# Raspberry_DC-HD_v1.net
KiCad netlist of a schematic drawn in Altium Designer
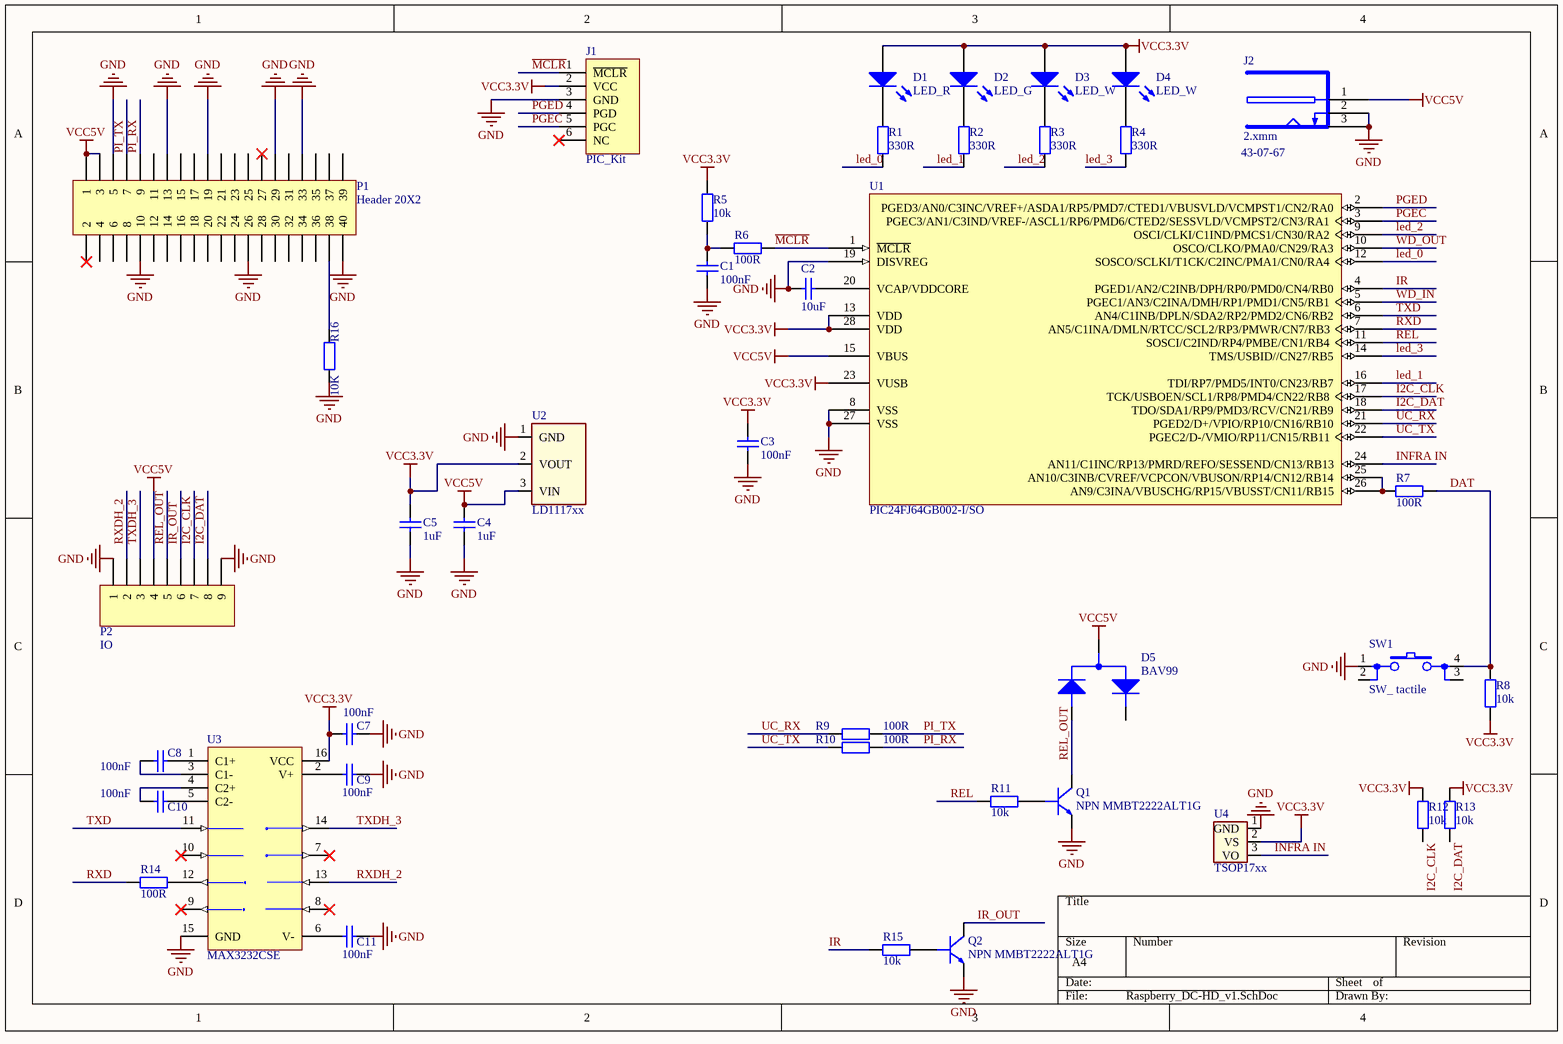
[diagram p0: Raspberry_DC-HD_v1.SchDoc]

(export (version "E")
  (design (tool "Eeschema 10.0.6"))
  (components
    (comp (ref "C1")
      (value "100nF")
      (footprint "FP_0603_CAP_080")
      (description "Capacitor")
      (libsource (lib "Capacitor") (part "CAP"))
    )
    (comp (ref "C2")
      (value "10uF")
      (footprint "FP_0603_CAP_080")
      (description "Capacitor")
      (libsource (lib "Capacitor") (part "CAP"))
    )
    (comp (ref "C3")
      (value "100nF")
      (footprint "FP_0603_CAP_080")
      (description "Capacitor")
      (libsource (lib "Capacitor") (part "CAP"))
    )
    (comp (ref "C4")
      (value "1uF")
      (footprint "FP_0603_CAP_080")
      (description "Capacitor")
      (libsource (lib "Capacitor") (part "CAP"))
    )
    (comp (ref "C5")
      (value "1uF")
      (footprint "FP_0603_CAP_080")
      (description "Capacitor")
      (libsource (lib "Capacitor") (part "CAP"))
    )
    (comp (ref "C7")
      (value "100nF")
      (footprint "FP_0603_CAP_080")
      (description "Capacitor")
      (libsource (lib "Capacitor") (part "CAP"))
    )
    (comp (ref "C8")
      (value "100nF")
      (footprint "FP_0603_CAP_080")
      (description "Capacitor")
      (libsource (lib "Capacitor") (part "CAP"))
    )
    (comp (ref "C9")
      (value "100nF")
      (footprint "FP_0603_CAP_080")
      (description "Capacitor")
      (libsource (lib "Capacitor") (part "CAP"))
    )
    (comp (ref "C10")
      (value "100nF")
      (footprint "FP_0603_CAP_080")
      (description "Capacitor")
      (libsource (lib "Capacitor") (part "CAP"))
    )
    (comp (ref "C11")
      (value "100nF")
      (footprint "FP_0603_CAP_080")
      (description "Capacitor")
      (libsource (lib "Capacitor") (part "CAP"))
    )
    (comp (ref "D1")
      (value "LED_R")
      (footprint "1206 LED Reversed")
      (description "Typical LED")
      (libsource (lib "Led_optical") (part "LED"))
    )
    (comp (ref "D2")
      (value "LED_G")
      (footprint "1206 LED Reversed")
      (description "Typical LED")
      (libsource (lib "Led_optical") (part "LED"))
    )
    (comp (ref "D3")
      (value "LED_W")
      (footprint "1206 LED Reversed")
      (description "Typical LED")
      (libsource (lib "Led_optical") (part "LED"))
    )
    (comp (ref "D4")
      (value "LED_W")
      (footprint "1206 LED Reversed")
      (description "Typical LED")
      (libsource (lib "Led_optical") (part "LED"))
    )
    (comp (ref "D5")
      (value "BAV99")
      (footprint "DIODE_SOT23_serial")
      (libsource (lib "Diode") (part "BAV99"))
    )
    (comp (ref "J1")
      (value "PIC_Kit")
      (footprint "HDR1X6")
      (description "PIC Kit connector")
      (libsource (lib "EtherIOv2") (part "PIC_Kit"))
    )
    (comp (ref "J2")
      (value "2.xmm")
      (footprint "FP_DC_TAP_ANYA")
      (description "2.xmm DC HEBA25 TÁPFESZÜLTSÉG ALJZAT ZÁRT, NYÁKBA 90°")
      (fields (field (name "ORDER INFO") "43-07-67"))
      (libsource (lib "Connector") (part "DC_TAP_ANYA"))
    )
    (comp (ref "P1")
      (value "Header 20X2")
      (footprint "Header_2X20_pin_2.54")
      (description "Header, 20-Pin, Dual row")
      (fields (field (name "PUBLISHER") "Altium Limited"))
      (libsource (lib "Miscellaneous Connectors") (part "Header 20X2"))
    )
    (comp (ref "P2")
      (value "IO")
      (footprint "Euroblock 3.5pitch 9P")
      (description "Header, 9-Pin")
      (fields (field (name "PUBLISHER") "Altium Limited"))
      (libsource (lib "Miscellaneous Connectors") (part "Header 9"))
    )
    (comp (ref "Q1")
      (value "NPN MMBT2222ALT1G")
      (footprint "TR_SOT23")
      (libsource (lib "Transistor") (part "NPN"))
    )
    (comp (ref "Q2")
      (value "NPN MMBT2222ALT1G")
      (footprint "TR_SOT23")
      (libsource (lib "Transistor") (part "NPN"))
    )
    (comp (ref "R1")
      (value "330R")
      (footprint "FP_0603_RES")
      (description "Resistor")
      (libsource (lib "Resistor") (part "RES"))
    )
    (comp (ref "R2")
      (value "330R")
      (footprint "FP_0603_RES")
      (description "Resistor")
      (libsource (lib "Resistor") (part "RES"))
    )
    (comp (ref "R3")
      (value "330R")
      (footprint "FP_0603_RES")
      (description "Resistor")
      (libsource (lib "Resistor") (part "RES"))
    )
    (comp (ref "R4")
      (value "330R")
      (footprint "FP_0603_RES")
      (description "Resistor")
      (libsource (lib "Resistor") (part "RES"))
    )
    (comp (ref "R5")
      (value "10k")
      (footprint "FP_0603_RES")
      (description "Resistor")
      (libsource (lib "") (part "Res3_1"))
    )
    (comp (ref "R6")
      (value "100R")
      (footprint "FP_0603_RES")
      (description "Resistor")
      (libsource (lib "") (part "RES_1"))
    )
    (comp (ref "R7")
      (value "100R")
      (footprint "FP_0603_RES")
      (description "Resistor")
      (libsource (lib "") (part "RES_1"))
    )
    (comp (ref "R8")
      (value "10k")
      (footprint "FP_0603_RES")
      (description "Resistor")
      (libsource (lib "") (part "Res3_1"))
    )
    (comp (ref "R9")
      (value "100R")
      (footprint "FP_0603_RES")
      (description "Resistor")
      (libsource (lib "") (part "RES_1"))
    )
    (comp (ref "R10")
      (value "100R")
      (footprint "FP_0603_RES")
      (description "Resistor")
      (libsource (lib "") (part "RES_1"))
    )
    (comp (ref "R11")
      (value "10k")
      (footprint "FP_0603_RES")
      (description "Resistor")
      (libsource (lib "Miscellaneous Devices") (part "Res3"))
    )
    (comp (ref "R12")
      (value "10k")
      (footprint "FP_0603_RES")
      (description "Resistor")
      (libsource (lib "") (part "Res3_1"))
    )
    (comp (ref "R13")
      (value "10k")
      (footprint "FP_0603_RES")
      (description "Resistor")
      (libsource (lib "") (part "Res3_1"))
    )
    (comp (ref "R14")
      (value "100R")
      (footprint "FP_0603_RES")
      (description "Resistor")
      (libsource (lib "") (part "RES_1"))
    )
    (comp (ref "R15")
      (value "10k")
      (footprint "FP_0603_RES")
      (description "Resistor")
      (libsource (lib "Miscellaneous Devices") (part "Res3"))
    )
    (comp (ref "R16")
      (value "10K")
      (footprint "FP_0603_RES")
      (description "Resistor")
      (libsource (lib "") (part "RES_2"))
    )
    (comp (ref "SW1")
      (value "SW_ tactile")
      (footprint "flat_smd_button")
      (libsource (lib "Switch") (part "SW_ tactile"))
    )
    (comp (ref "U1")
      (value "PIC24FJ64GB002-I/SO")
      (footprint "SSOP-28")
      (fields (field (name "PUBLISHER") "Altium Limited"))
      (libsource (lib "Waterstars") (part "PIC24FJ64GB002-I/SO"))
    )
    (comp (ref "U2")
      (value "LD1117xx")
      (footprint "SUPPLY_SOT223")
      (description "LD1117xx 3,3V lin reg")
      (libsource (lib "Supply") (part "LD1117xx"))
    )
    (comp (ref "U3")
      (value "MAX3232CSE")
      (footprint "DIGITAL_SOIC16")
      (description "3.0V TO 5.5V, Low-Power, up to 1Mbps, True RS-232 Transceiver Using Four 0.1µF External Capacitor")
      (fields (field (name "PUBLISHER") "Altium Limited"))
      (libsource (lib "Maxim Communication Transceiver") (part "MAX3232CSE"))
    )
    (comp (ref "U4")
      (value "TSOP17xx")
      (footprint "TSOP17xx")
      (description "TSOP17xx IR receiver")
      (libsource (lib "Sensor") (part "TSOP17xx"))
    )
  )
  (nets
    (net (code "1") (name "/DAT") (class "Default")
      (node (ref "R7") (pin "1") (pinfunction "1_1") (pintype "passive"))
      (node (ref "R8") (pin "1") (pinfunction "1_1") (pintype "passive"))
      (node (ref "SW1") (pin "4") (pinfunction "4_4") (pintype "passive"))
    )
    (net (code "2") (name "/I2C_CLK") (class "Default")
      (node (ref "P2") (pin "7") (pinfunction "7_7") (pintype "passive"))
      (node (ref "R12") (pin "2") (pinfunction "2_2") (pintype "passive"))
      (node (ref "U1") (pin "17") (pinfunction "TCK/USBOEN/SCL1/RP8/PMD4/CN22/RB8_17") (pintype "bidirectional"))
    )
    (net (code "3") (name "/I2C_DAT") (class "Default")
      (node (ref "P2") (pin "8") (pinfunction "8_8") (pintype "passive"))
      (node (ref "R13") (pin "2") (pinfunction "2_2") (pintype "passive"))
      (node (ref "U1") (pin "18") (pinfunction "TDO/SDA1/RP9/PMD3/RCV/CN21/RB9_18") (pintype "bidirectional"))
    )
    (net (code "4") (name "/INFRA IN") (class "Default")
      (node (ref "U1") (pin "24") (pinfunction "AN11/C1INC/RP13/PMRD/REFO/SESSEND/CN13/RB13_24") (pintype "bidirectional"))
      (node (ref "U4") (pin "3") (pinfunction "VO_3") (pintype "passive"))
    )
    (net (code "5") (name "/IR") (class "Default")
      (node (ref "R15") (pin "1") (pinfunction "1_1") (pintype "passive"))
      (node (ref "U1") (pin "4") (pinfunction "PGED1/AN2/C2INB/DPH/RP0/PMD0/CN4/RB0_4") (pintype "bidirectional"))
    )
    (net (code "6") (name "/IR_OUT") (class "Default")
      (node (ref "P2") (pin "6") (pinfunction "6_6") (pintype "passive"))
      (node (ref "Q2") (pin "C") (pinfunction "C_C") (pintype "passive"))
    )
    (net (code "7") (name "/PGEC") (class "Default")
      (node (ref "J1") (pin "5") (pinfunction "PGC_5") (pintype "passive"))
      (node (ref "U1") (pin "3") (pinfunction "PGEC3/AN1/C3IND/VREF-/ASCL1/RP6/PMD6/CTED2/SESSVLD/VCMPST2/CN3/RA1_3") (pintype "bidirectional"))
    )
    (net (code "8") (name "/PGED") (class "Default")
      (node (ref "J1") (pin "4") (pinfunction "PGD_4") (pintype "passive"))
      (node (ref "U1") (pin "2") (pinfunction "PGED3/AN0/C3INC/VREF+/ASDA1/RP5/PMD7/CTED1/VBUSVLD/VCMPST1/CN2/RA0_2") (pintype "bidirectional"))
    )
    (net (code "9") (name "/PI_RX") (class "Default")
      (node (ref "P1") (pin "9") (pinfunction "9_9") (pintype "passive"))
      (node (ref "R10") (pin "1") (pinfunction "1_1") (pintype "passive"))
    )
    (net (code "10") (name "/PI_TX") (class "Default")
      (node (ref "P1") (pin "7") (pinfunction "7_7") (pintype "passive"))
      (node (ref "R9") (pin "1") (pinfunction "1_1") (pintype "passive"))
    )
    (net (code "11") (name "/REL") (class "Default")
      (node (ref "R11") (pin "1") (pinfunction "1_1") (pintype "passive"))
      (node (ref "U1") (pin "11") (pinfunction "SOSCI/C2IND/RP4/PMBE/CN1/RB4_11") (pintype "bidirectional"))
    )
    (net (code "12") (name "/REL_OUT") (class "Default")
      (node (ref "D5") (pin "A") (pinfunction "A_A") (pintype "passive"))
      (node (ref "P2") (pin "5") (pinfunction "5_5") (pintype "passive"))
      (node (ref "Q1") (pin "C") (pinfunction "C_C") (pintype "passive"))
    )
    (net (code "13") (name "/RXD") (class "Default")
      (node (ref "R14") (pin "2") (pinfunction "2_2") (pintype "passive"))
      (node (ref "U1") (pin "7") (pinfunction "AN5/C1INA/DMLN/RTCC/SCL2/RP3/PMWR/CN7/RB3_7") (pintype "bidirectional"))
    )
    (net (code "14") (name "/RXDH_2") (class "Default")
      (node (ref "P2") (pin "2") (pinfunction "2_2") (pintype "passive"))
      (node (ref "U3") (pin "13") (pinfunction "R1IN_13") (pintype "input"))
    )
    (net (code "15") (name "/TXD") (class "Default")
      (node (ref "U1") (pin "6") (pinfunction "AN4/C1INB/DPLN/SDA2/RP2/PMD2/CN6/RB2_6") (pintype "bidirectional"))
      (node (ref "U3") (pin "11") (pinfunction "T1IN_11") (pintype "input"))
    )
    (net (code "16") (name "/TXDH_3") (class "Default")
      (node (ref "P2") (pin "3") (pinfunction "3_3") (pintype "passive"))
      (node (ref "U3") (pin "14") (pinfunction "T1OUT_14") (pintype "output"))
    )
    (net (code "17") (name "/UC_RX") (class "Default")
      (node (ref "R9") (pin "2") (pinfunction "2_2") (pintype "passive"))
      (node (ref "U1") (pin "21") (pinfunction "PGED2/D+/VPIO/RP10/CN16/RB10_21") (pintype "bidirectional"))
    )
    (net (code "18") (name "/UC_TX") (class "Default")
      (node (ref "R10") (pin "2") (pinfunction "2_2") (pintype "passive"))
      (node (ref "U1") (pin "22") (pinfunction "PGEC2/D-/VMIO/RP11/CN15/RB11_22") (pintype "bidirectional"))
    )
    (net (code "19") (name "/WD_IN") (class "Default")
      (node (ref "U1") (pin "5") (pinfunction "PGEC1/AN3/C2INA/DMH/RP1/PMD1/CN5/RB1_5") (pintype "bidirectional"))
    )
    (net (code "20") (name "/WD_OUT") (class "Default")
      (node (ref "U1") (pin "10") (pinfunction "OSCO/CLKO/PMA0/CN29/RA3_10") (pintype "bidirectional"))
    )
    (net (code "21") (name "/led_0") (class "Default")
      (node (ref "R1") (pin "2") (pinfunction "2_2") (pintype "passive"))
      (node (ref "U1") (pin "12") (pinfunction "SOSCO/SCLKI/T1CK/C2INC/PMA1/CN0/RA4_12") (pintype "bidirectional"))
    )
    (net (code "22") (name "/led_1") (class "Default")
      (node (ref "R2") (pin "2") (pinfunction "2_2") (pintype "passive"))
      (node (ref "U1") (pin "16") (pinfunction "TDI/RP7/PMD5/INT0/CN23/RB7_16") (pintype "bidirectional"))
    )
    (net (code "23") (name "/led_2") (class "Default")
      (node (ref "R3") (pin "2") (pinfunction "2_2") (pintype "passive"))
      (node (ref "U1") (pin "9") (pinfunction "OSCI/CLKI/C1IND/PMCS1/CN30/RA2_9") (pintype "bidirectional"))
    )
    (net (code "24") (name "/led_3") (class "Default")
      (node (ref "R4") (pin "2") (pinfunction "2_2") (pintype "passive"))
      (node (ref "U1") (pin "14") (pinfunction "TMS/USBID//CN27/RB5_14") (pintype "bidirectional"))
    )
    (net (code "25") (name "/~{MCLR}") (class "Default")
      (node (ref "J1") (pin "1") (pinfunction "~{MCLR}_1") (pintype "passive"))
      (node (ref "R6") (pin "1") (pinfunction "1_1") (pintype "passive"))
      (node (ref "U1") (pin "1") (pinfunction "~{MCLR}_1") (pintype "input"))
    )
    (net (code "26") (name "GND") (class "Default")
      (node (ref "C1") (pin "1") (pinfunction "1_1") (pintype "passive"))
      (node (ref "C11") (pin "2") (pinfunction "2_2") (pintype "passive"))
      (node (ref "C2") (pin "2") (pinfunction "2_2") (pintype "passive"))
      (node (ref "C3") (pin "1") (pinfunction "1_1") (pintype "passive"))
      (node (ref "C4") (pin "1") (pinfunction "1_1") (pintype "passive"))
      (node (ref "C5") (pin "1") (pinfunction "1_1") (pintype "passive"))
      (node (ref "C7") (pin "2") (pinfunction "2_2") (pintype "passive"))
      (node (ref "C9") (pin "2") (pinfunction "2_2") (pintype "passive"))
      (node (ref "J1") (pin "3") (pinfunction "GND_3") (pintype "passive"))
      (node (ref "J2") (pin "2") (pinfunction "GND_2") (pintype "power_in"))
      (node (ref "J2") (pin "3") (pinfunction "GND_3") (pintype "power_in"))
      (node (ref "P1") (pin "10") (pinfunction "10_10") (pintype "passive"))
      (node (ref "P1") (pin "13") (pinfunction "13_13") (pintype "passive"))
      (node (ref "P1") (pin "19") (pinfunction "19_19") (pintype "passive"))
      (node (ref "P1") (pin "26") (pinfunction "26_26") (pintype "passive"))
      (node (ref "P1") (pin "29") (pinfunction "29_29") (pintype "passive"))
      (node (ref "P1") (pin "33") (pinfunction "33_33") (pintype "passive"))
      (node (ref "P1") (pin "40") (pinfunction "40_40") (pintype "passive"))
      (node (ref "P1") (pin "5") (pinfunction "5_5") (pintype "passive"))
      (node (ref "P2") (pin "1") (pinfunction "1_1") (pintype "passive"))
      (node (ref "P2") (pin "9") (pinfunction "9_9") (pintype "passive"))
      (node (ref "Q1") (pin "E") (pinfunction "E_E") (pintype "passive"))
      (node (ref "Q2") (pin "E") (pinfunction "E_E") (pintype "passive"))
      (node (ref "R16") (pin "1") (pinfunction "1_1") (pintype "passive"))
      (node (ref "SW1") (pin "1") (pinfunction "1_1") (pintype "passive"))
      (node (ref "U1") (pin "19") (pinfunction "DISVREG_19") (pintype "input"))
      (node (ref "U1") (pin "27") (pinfunction "VSS_27") (pintype "power_in"))
      (node (ref "U1") (pin "8") (pinfunction "VSS_8") (pintype "power_in"))
      (node (ref "U2") (pin "1") (pinfunction "GND_1") (pintype "passive"))
      (node (ref "U3") (pin "15") (pinfunction "GND_15") (pintype "power_in"))
      (node (ref "U4") (pin "1") (pinfunction "GND_1") (pintype "passive"))
    )
    (net (code "27") (name "Net-(C1-Pad2)") (class "Default")
      (node (ref "C1") (pin "2") (pinfunction "2_2") (pintype "passive"))
      (node (ref "R5") (pin "2") (pinfunction "2_2") (pintype "passive"))
      (node (ref "R6") (pin "2") (pinfunction "2_2") (pintype "passive"))
    )
    (net (code "28") (name "Net-(D1-K)") (class "Default")
      (node (ref "D1") (pin "2") (pinfunction "K_2") (pintype "passive"))
      (node (ref "R1") (pin "1") (pinfunction "1_1") (pintype "passive"))
    )
    (net (code "29") (name "Net-(D2-K)") (class "Default")
      (node (ref "D2") (pin "2") (pinfunction "K_2") (pintype "passive"))
      (node (ref "R2") (pin "1") (pinfunction "1_1") (pintype "passive"))
    )
    (net (code "30") (name "Net-(D3-K)") (class "Default")
      (node (ref "D3") (pin "2") (pinfunction "K_2") (pintype "passive"))
      (node (ref "R3") (pin "1") (pinfunction "1_1") (pintype "passive"))
    )
    (net (code "31") (name "Net-(D4-K)") (class "Default")
      (node (ref "D4") (pin "2") (pinfunction "K_2") (pintype "passive"))
      (node (ref "R4") (pin "1") (pinfunction "1_1") (pintype "passive"))
    )
    (net (code "32") (name "Net-(P1-Pad38)") (class "Default")
      (node (ref "P1") (pin "38") (pinfunction "38_38") (pintype "passive"))
      (node (ref "R16") (pin "2") (pinfunction "2_2") (pintype "passive"))
    )
    (net (code "33") (name "Net-(Q1-PadB)") (class "Default")
      (node (ref "Q1") (pin "B") (pinfunction "B_B") (pintype "passive"))
      (node (ref "R11") (pin "2") (pinfunction "2_2") (pintype "passive"))
    )
    (net (code "34") (name "Net-(Q2-PadB)") (class "Default")
      (node (ref "Q2") (pin "B") (pinfunction "B_B") (pintype "passive"))
      (node (ref "R15") (pin "2") (pinfunction "2_2") (pintype "passive"))
    )
    (net (code "35") (name "Net-(U1-AN10{slash}C3INB{slash}CVREF{slash}VCPCON{slash}VBUSON{slash}RP14{slash}CN12{slash}RB14)") (class "Default")
      (node (ref "R7") (pin "2") (pinfunction "2_2") (pintype "passive"))
      (node (ref "U1") (pin "25") (pinfunction "AN10/C3INB/CVREF/VCPCON/VBUSON/RP14/CN12/RB14_25") (pintype "bidirectional"))
      (node (ref "U1") (pin "26") (pinfunction "AN9/C3INA/VBUSCHG/RP15/VBUSST/CN11/RB15_26") (pintype "bidirectional"))
    )
    (net (code "36") (name "Net-(U1-VCAP{slash}VDDCORE)") (class "Default")
      (node (ref "C2") (pin "1") (pinfunction "1_1") (pintype "passive"))
      (node (ref "U1") (pin "20") (pinfunction "VCAP/VDDCORE_20") (pintype "power_in"))
    )
    (net (code "37") (name "Net-(U3-C1+)") (class "Default")
      (node (ref "C8") (pin "2") (pinfunction "2_2") (pintype "passive"))
      (node (ref "U3") (pin "1") (pinfunction "C1+_1") (pintype "passive"))
    )
    (net (code "38") (name "Net-(U3-C1-)") (class "Default")
      (node (ref "C8") (pin "1") (pinfunction "1_1") (pintype "passive"))
      (node (ref "U3") (pin "3") (pinfunction "C1-_3") (pintype "passive"))
    )
    (net (code "39") (name "Net-(U3-C2+)") (class "Default")
      (node (ref "C10") (pin "1") (pinfunction "1_1") (pintype "passive"))
      (node (ref "U3") (pin "4") (pinfunction "C2+_4") (pintype "passive"))
    )
    (net (code "40") (name "Net-(U3-C2-)") (class "Default")
      (node (ref "C10") (pin "2") (pinfunction "2_2") (pintype "passive"))
      (node (ref "U3") (pin "5") (pinfunction "C2-_5") (pintype "passive"))
    )
    (net (code "41") (name "Net-(U3-R1OUT)") (class "Default")
      (node (ref "R14") (pin "1") (pinfunction "1_1") (pintype "passive"))
      (node (ref "U3") (pin "12") (pinfunction "R1OUT_12") (pintype "output"))
    )
    (net (code "42") (name "Net-(U3-V+)") (class "Default")
      (node (ref "C9") (pin "1") (pinfunction "1_1") (pintype "passive"))
      (node (ref "U3") (pin "2") (pinfunction "V+_2") (pintype "power_in"))
    )
    (net (code "43") (name "Net-(U3-V-)") (class "Default")
      (node (ref "C11") (pin "1") (pinfunction "1_1") (pintype "passive"))
      (node (ref "U3") (pin "6") (pinfunction "V-_6") (pintype "power_in"))
    )
    (net (code "44") (name "VCC3.3V") (class "Default")
      (node (ref "C3") (pin "2") (pinfunction "2_2") (pintype "passive"))
      (node (ref "C5") (pin "2") (pinfunction "2_2") (pintype "passive"))
      (node (ref "C7") (pin "1") (pinfunction "1_1") (pintype "passive"))
      (node (ref "D1") (pin "1") (pinfunction "A_1") (pintype "passive"))
      (node (ref "D2") (pin "1") (pinfunction "A_1") (pintype "passive"))
      (node (ref "D3") (pin "1") (pinfunction "A_1") (pintype "passive"))
      (node (ref "D4") (pin "1") (pinfunction "A_1") (pintype "passive"))
      (node (ref "J1") (pin "2") (pinfunction "VCC_2") (pintype "passive"))
      (node (ref "R12") (pin "1") (pinfunction "1_1") (pintype "passive"))
      (node (ref "R13") (pin "1") (pinfunction "1_1") (pintype "passive"))
      (node (ref "R5") (pin "1") (pinfunction "1_1") (pintype "passive"))
      (node (ref "R8") (pin "2") (pinfunction "2_2") (pintype "passive"))
      (node (ref "U1") (pin "13") (pinfunction "VDD_13") (pintype "power_in"))
      (node (ref "U1") (pin "23") (pinfunction "VUSB_23") (pintype "power_in"))
      (node (ref "U1") (pin "28") (pinfunction "VDD_28") (pintype "power_in"))
      (node (ref "U2") (pin "2") (pinfunction "VOUT_2") (pintype "passive"))
      (node (ref "U3") (pin "16") (pinfunction "VCC_16") (pintype "power_in"))
      (node (ref "U4") (pin "2") (pinfunction "VS_2") (pintype "passive"))
    )
    (net (code "45") (name "VCC5V") (class "Default")
      (node (ref "C4") (pin "2") (pinfunction "2_2") (pintype "passive"))
      (node (ref "D5") (pin "COM") (pinfunction "COM_COM") (pintype "passive"))
      (node (ref "J2") (pin "1") (pinfunction "9V_1") (pintype "power_in"))
      (node (ref "P1") (pin "1") (pinfunction "1_1") (pintype "passive"))
      (node (ref "P1") (pin "3") (pinfunction "3_3") (pintype "passive"))
      (node (ref "P2") (pin "4") (pinfunction "4_4") (pintype "passive"))
      (node (ref "U1") (pin "15") (pinfunction "VBUS_15") (pintype "power_in"))
      (node (ref "U2") (pin "3") (pinfunction "VIN_3") (pintype "passive"))
    )
    (net (code "46") (name "unconnected-(D5-PadK)") (class "Default")
      (node (ref "D5") (pin "K") (pinfunction "K_K") (pintype "passive"))
    )
    (net (code "47") (name "unconnected-(J1-NC-Pad6)") (class "Default")
      (node (ref "J1") (pin "6") (pinfunction "NC_6") (pintype "passive+no_connect"))
    )
    (net (code "48") (name "unconnected-(P1-Pad2)") (class "Default")
      (node (ref "P1") (pin "2") (pinfunction "2_2") (pintype "passive+no_connect"))
    )
    (net (code "49") (name "unconnected-(P1-Pad4)") (class "Default")
      (node (ref "P1") (pin "4") (pinfunction "4_4") (pintype "passive"))
    )
    (net (code "50") (name "unconnected-(P1-Pad6)") (class "Default")
      (node (ref "P1") (pin "6") (pinfunction "6_6") (pintype "passive"))
    )
    (net (code "51") (name "unconnected-(P1-Pad8)") (class "Default")
      (node (ref "P1") (pin "8") (pinfunction "8_8") (pintype "passive"))
    )
    (net (code "52") (name "unconnected-(P1-Pad11)") (class "Default")
      (node (ref "P1") (pin "11") (pinfunction "11_11") (pintype "passive"))
    )
    (net (code "53") (name "unconnected-(P1-Pad12)") (class "Default")
      (node (ref "P1") (pin "12") (pinfunction "12_12") (pintype "passive"))
    )
    (net (code "54") (name "unconnected-(P1-Pad14)") (class "Default")
      (node (ref "P1") (pin "14") (pinfunction "14_14") (pintype "passive"))
    )
    (net (code "55") (name "unconnected-(P1-Pad15)") (class "Default")
      (node (ref "P1") (pin "15") (pinfunction "15_15") (pintype "passive"))
    )
    (net (code "56") (name "unconnected-(P1-Pad16)") (class "Default")
      (node (ref "P1") (pin "16") (pinfunction "16_16") (pintype "passive"))
    )
    (net (code "57") (name "unconnected-(P1-Pad17)") (class "Default")
      (node (ref "P1") (pin "17") (pinfunction "17_17") (pintype "passive"))
    )
    (net (code "58") (name "unconnected-(P1-Pad18)") (class "Default")
      (node (ref "P1") (pin "18") (pinfunction "18_18") (pintype "passive"))
    )
    (net (code "59") (name "unconnected-(P1-Pad20)") (class "Default")
      (node (ref "P1") (pin "20") (pinfunction "20_20") (pintype "passive"))
    )
    (net (code "60") (name "unconnected-(P1-Pad21)") (class "Default")
      (node (ref "P1") (pin "21") (pinfunction "21_21") (pintype "passive"))
    )
    (net (code "61") (name "unconnected-(P1-Pad22)") (class "Default")
      (node (ref "P1") (pin "22") (pinfunction "22_22") (pintype "passive"))
    )
    (net (code "62") (name "unconnected-(P1-Pad23)") (class "Default")
      (node (ref "P1") (pin "23") (pinfunction "23_23") (pintype "passive"))
    )
    (net (code "63") (name "unconnected-(P1-Pad24)") (class "Default")
      (node (ref "P1") (pin "24") (pinfunction "24_24") (pintype "passive"))
    )
    (net (code "64") (name "unconnected-(P1-Pad25)") (class "Default")
      (node (ref "P1") (pin "25") (pinfunction "25_25") (pintype "passive"))
    )
    (net (code "65") (name "unconnected-(P1-Pad27)") (class "Default")
      (node (ref "P1") (pin "27") (pinfunction "27_27") (pintype "passive+no_connect"))
    )
    (net (code "66") (name "unconnected-(P1-Pad28)") (class "Default")
      (node (ref "P1") (pin "28") (pinfunction "28_28") (pintype "passive"))
    )
    (net (code "67") (name "unconnected-(P1-Pad30)") (class "Default")
      (node (ref "P1") (pin "30") (pinfunction "30_30") (pintype "passive"))
    )
    (net (code "68") (name "unconnected-(P1-Pad31)") (class "Default")
      (node (ref "P1") (pin "31") (pinfunction "31_31") (pintype "passive"))
    )
    (net (code "69") (name "unconnected-(P1-Pad32)") (class "Default")
      (node (ref "P1") (pin "32") (pinfunction "32_32") (pintype "passive"))
    )
    (net (code "70") (name "unconnected-(P1-Pad34)") (class "Default")
      (node (ref "P1") (pin "34") (pinfunction "34_34") (pintype "passive"))
    )
    (net (code "71") (name "unconnected-(P1-Pad35)") (class "Default")
      (node (ref "P1") (pin "35") (pinfunction "35_35") (pintype "passive"))
    )
    (net (code "72") (name "unconnected-(P1-Pad36)") (class "Default")
      (node (ref "P1") (pin "36") (pinfunction "36_36") (pintype "passive"))
    )
    (net (code "73") (name "unconnected-(P1-Pad37)") (class "Default")
      (node (ref "P1") (pin "37") (pinfunction "37_37") (pintype "passive"))
    )
    (net (code "74") (name "unconnected-(P1-Pad39)") (class "Default")
      (node (ref "P1") (pin "39") (pinfunction "39_39") (pintype "passive"))
    )
    (net (code "75") (name "unconnected-(SW1-Pad2)") (class "Default")
      (node (ref "SW1") (pin "2") (pinfunction "2_2") (pintype "passive"))
    )
    (net (code "76") (name "unconnected-(SW1-Pad3)") (class "Default")
      (node (ref "SW1") (pin "3") (pinfunction "3_3") (pintype "passive"))
    )
    (net (code "77") (name "unconnected-(U3-R2IN-Pad8)") (class "Default")
      (node (ref "U3") (pin "8") (pinfunction "R2IN_8") (pintype "input+no_connect"))
    )
    (net (code "78") (name "unconnected-(U3-R2OUT-Pad9)") (class "Default")
      (node (ref "U3") (pin "9") (pinfunction "R2OUT_9") (pintype "output+no_connect"))
    )
    (net (code "79") (name "unconnected-(U3-T2IN-Pad10)") (class "Default")
      (node (ref "U3") (pin "10") (pinfunction "T2IN_10") (pintype "input+no_connect"))
    )
    (net (code "80") (name "unconnected-(U3-T2OUT-Pad7)") (class "Default")
      (node (ref "U3") (pin "7") (pinfunction "T2OUT_7") (pintype "output+no_connect"))
    )
  )
)
